# 105358-3SC002-01-A_BlockDiagram.net
KiCad netlist of a schematic drawn in Altium Designer
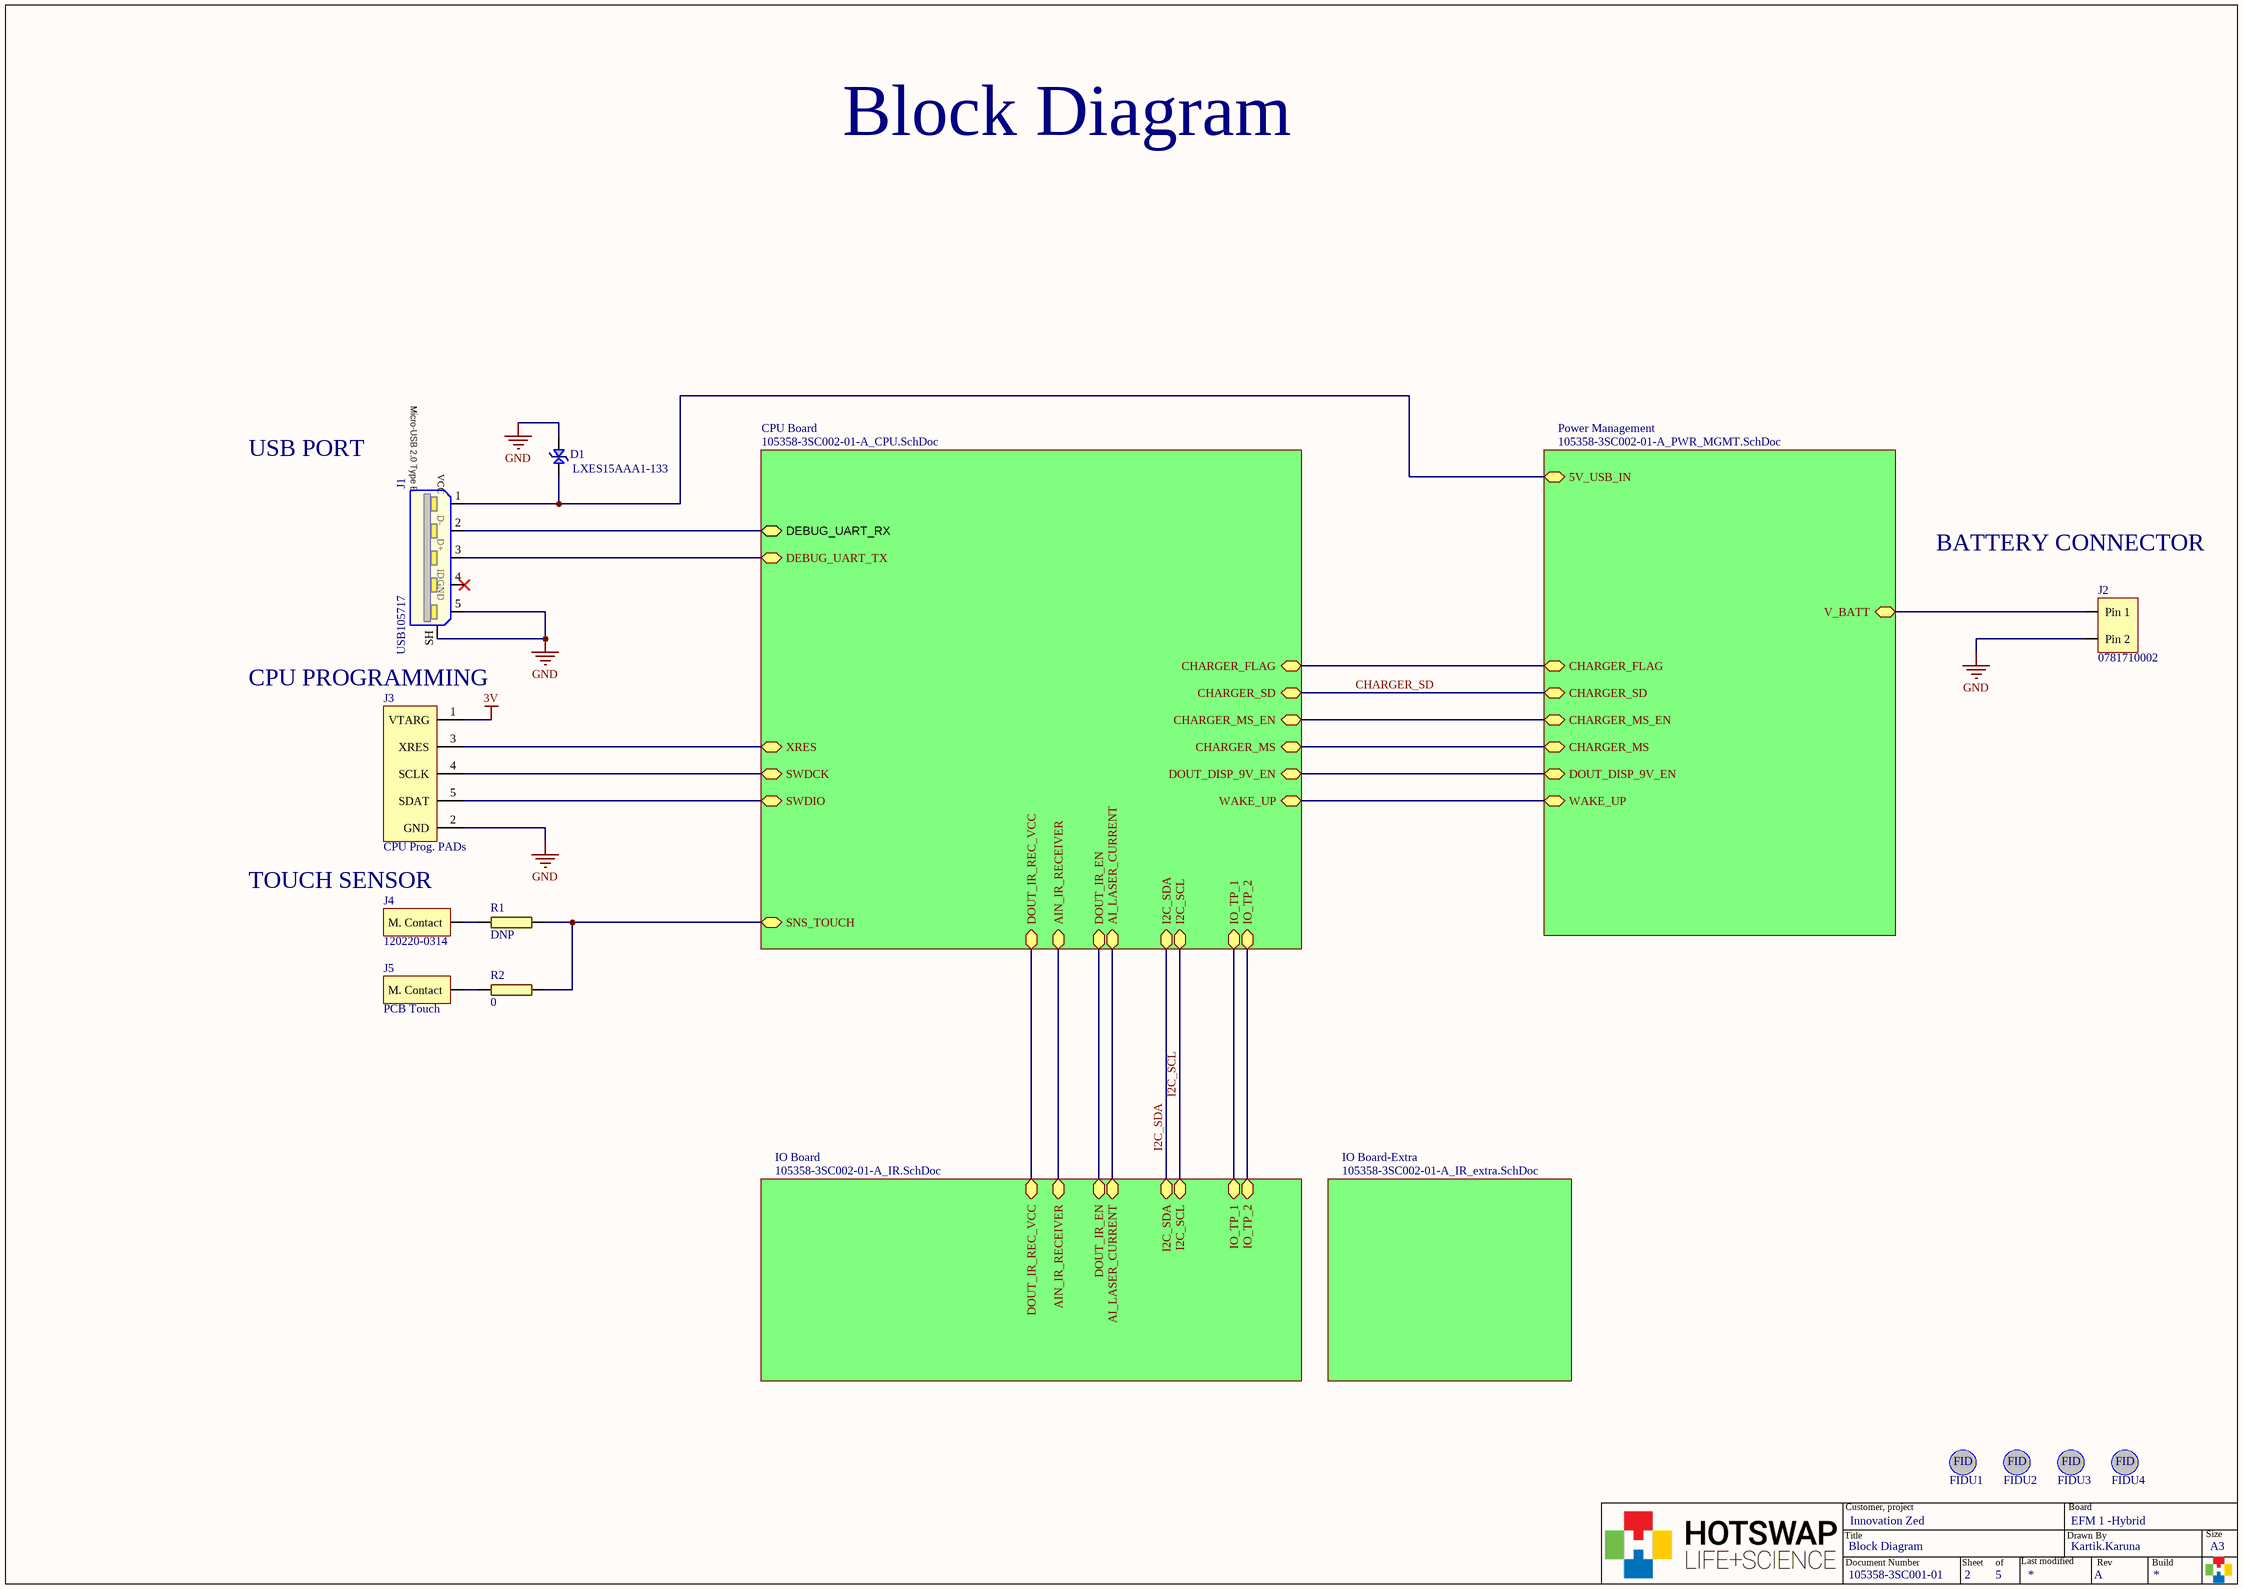
[diagram p0: 105358-3SC002-01-A_BlockDiagram.SchDoc]

(export (version "E")
  (design (tool "Eeschema 10.0.6"))
  (components
    (comp (ref "D1")
      (value "LXES15AAA1-133")
      (footprint "0402C-GENERIC")
      (description "TVS DIODE 15VWM 0402")
      (fields
        (field (name "MANUFACTURER") "Murata Electronics North America")
        (field (name "DIGI-KEY PART NUMBER") "490-13209-1-ND")
      )
      (libsource (lib "ConnectMedical") (part "TVS DIODE 15VWM 0402"))
    )
    (comp (ref "FIDU1")
      (value "FIDU-miniROUND")
      (footprint "FIDU-MINI-ROUND")
      (libsource (lib "ConnectMedical") (part "FIDU-miniROUND"))
    )
    (comp (ref "FIDU2")
      (value "FIDU-miniROUND")
      (footprint "FIDU-MINI-ROUND")
      (libsource (lib "ConnectMedical") (part "FIDU-miniROUND"))
    )
    (comp (ref "FIDU3")
      (value "FIDU-miniROUND")
      (footprint "FIDU-MINI-ROUND")
      (libsource (lib "ConnectMedical") (part "FIDU-miniROUND"))
    )
    (comp (ref "FIDU4")
      (value "FIDU-miniROUND")
      (footprint "FIDU-MINI-ROUND")
      (libsource (lib "ConnectMedical") (part "FIDU-miniROUND"))
    )
    (comp (ref "J1")
      (value "USB105717")
      (footprint "UUSB_MOLEX105017")
      (description "CONN RCPT USB-micro")
      (fields (field (name "MANUFACTURER") "Molex") (field (name "MANUFACTURER PART NUMBER") "105017"))
      (libsource (lib "ConnectMedical") (part "USB105717"))
    )
    (comp (ref "J2")
      (value "0781710002")
      (footprint "PAD 0781710002")
      (description "1.20MM WTB HEADER VERT 2POS")
      (fields (field (name "MANUFACTURER") "Molex, LLC") (field (name "DIGI-KEY PART NUMBER") "WM4459CT-ND"))
      (libsource (lib "ConnectMedical") (part "CONNECTOR 1.20MM WTB HEADER VERT 2POS"))
    )
    (comp (ref "J3")
      (value "CPU Prog. PADs")
      (footprint "PAD PROGRAMMING")
      (description "CPU Programming PADs")
      (libsource (lib "ConnectMedical") (part "PROGRAMMING PADS"))
    )
    (comp (ref "J4")
      (value "120220-0314")
      (footprint "PAD 1.0x1.95mm")
      (description "MICRO UNIVERSAL CONTACT Z 3.5MM")
      (fields
        (field (name "MANUFACTURER") "ITT Cannon, LLC")
        (field (name "DIGI-KEY PART NUMBER") "1003-2383-1-ND")
      )
      (libsource (lib "ConnectMedical") (part "MICRO UNIVERSAL CONTACT Z 3.5MM"))
    )
    (comp (ref "J5")
      (value "PCB Touch")
      (footprint "Touch_PAD")
      (description "PCB Touch PAD")
      (libsource (lib "ConnectMedical") (part "PCB Touch"))
    )
    (comp (ref "R1")
      (value "DNP")
      (footprint "0402R-GENERIC")
      (libsource (lib "ConnectMedical") (part "0402R-Do Not Place"))
    )
    (comp (ref "R2")
      (value "0")
      (footprint "0402R-GENERIC")
      (description "RES SMD 0.0OHM JUMPER 1/16W 0402")
      (fields (field (name "DIGI-KEY PART NUMBER") "311-0.0JRCT-ND") (field (name "MANUFACTURER") "Yageo"))
      (libsource (lib "ConnectMedical") (part "0402R-0 OHM-0.063W"))
    )
  )
  (nets
    (net (code "1") (name "/5V_USB_IN") (class "Default")
      (node (ref "D1") (pin "2") (pinfunction "2_2") (pintype "passive"))
      (node (ref "J1") (pin "1") (pinfunction "VCC_1") (pintype "passive"))
    )
    (net (code "8") (name "/DEBUG_UART_RX") (class "Default")
      (node (ref "J1") (pin "2") (pinfunction "D-_2") (pintype "passive"))
    )
    (net (code "9") (name "/DEBUG_UART_TX") (class "Default")
      (node (ref "J1") (pin "3") (pinfunction "D+_3") (pintype "passive"))
    )
    (net (code "17") (name "/SNS_TOUCH") (class "Default")
      (node (ref "R1") (pin "2") (pintype "passive"))
      (node (ref "R2") (pin "2") (pintype "passive"))
    )
    (net (code "18") (name "/SWDCK") (class "Default")
      (node (ref "J3") (pin "4") (pinfunction "SCLK_4") (pintype "passive"))
    )
    (net (code "19") (name "/SWDIO") (class "Default")
      (node (ref "J3") (pin "5") (pinfunction "SDAT_5") (pintype "passive"))
    )
    (net (code "20") (name "/V_BATT") (class "Default")
      (node (ref "J2") (pin "1") (pinfunction "Pin_1_1") (pintype "passive"))
    )
    (net (code "22") (name "/XRES") (class "Default")
      (node (ref "J3") (pin "3") (pinfunction "XRES_3") (pintype "passive"))
    )
    (net (code "23") (name "3V") (class "Default")
      (node (ref "J3") (pin "1") (pinfunction "VTARG_1") (pintype "passive"))
    )
    (net (code "24") (name "GND") (class "Default")
      (node (ref "D1") (pin "1") (pinfunction "1_1") (pintype "passive"))
      (node (ref "J1") (pin "5") (pinfunction "GND_5") (pintype "passive"))
      (node (ref "J1") (pin "SH") (pinfunction "Shell_SH") (pintype "passive"))
      (node (ref "J2") (pin "2") (pinfunction "Pin_2_2") (pintype "passive"))
      (node (ref "J3") (pin "2") (pinfunction "GND_2") (pintype "passive"))
    )
    (net (code "25") (name "Net-(J4-M._Contact)") (class "Default")
      (node (ref "J4") (pin "1") (pinfunction "M._Contact_1") (pintype "passive"))
      (node (ref "R1") (pin "1") (pintype "passive"))
    )
    (net (code "26") (name "Net-(J5-M._Contact)") (class "Default")
      (node (ref "J5") (pin "1") (pinfunction "M._Contact_1") (pintype "passive"))
      (node (ref "R2") (pin "1") (pintype "passive"))
    )
    (net (code "27") (name "unconnected-(J1-ID-Pad4)") (class "Default")
      (node (ref "J1") (pin "4") (pinfunction "ID_4") (pintype "passive+no_connect"))
    )
  )
)
